# tick-box-1591A-mk-5_0.net
KiCad netlist of a schematic drawn in EAGLE
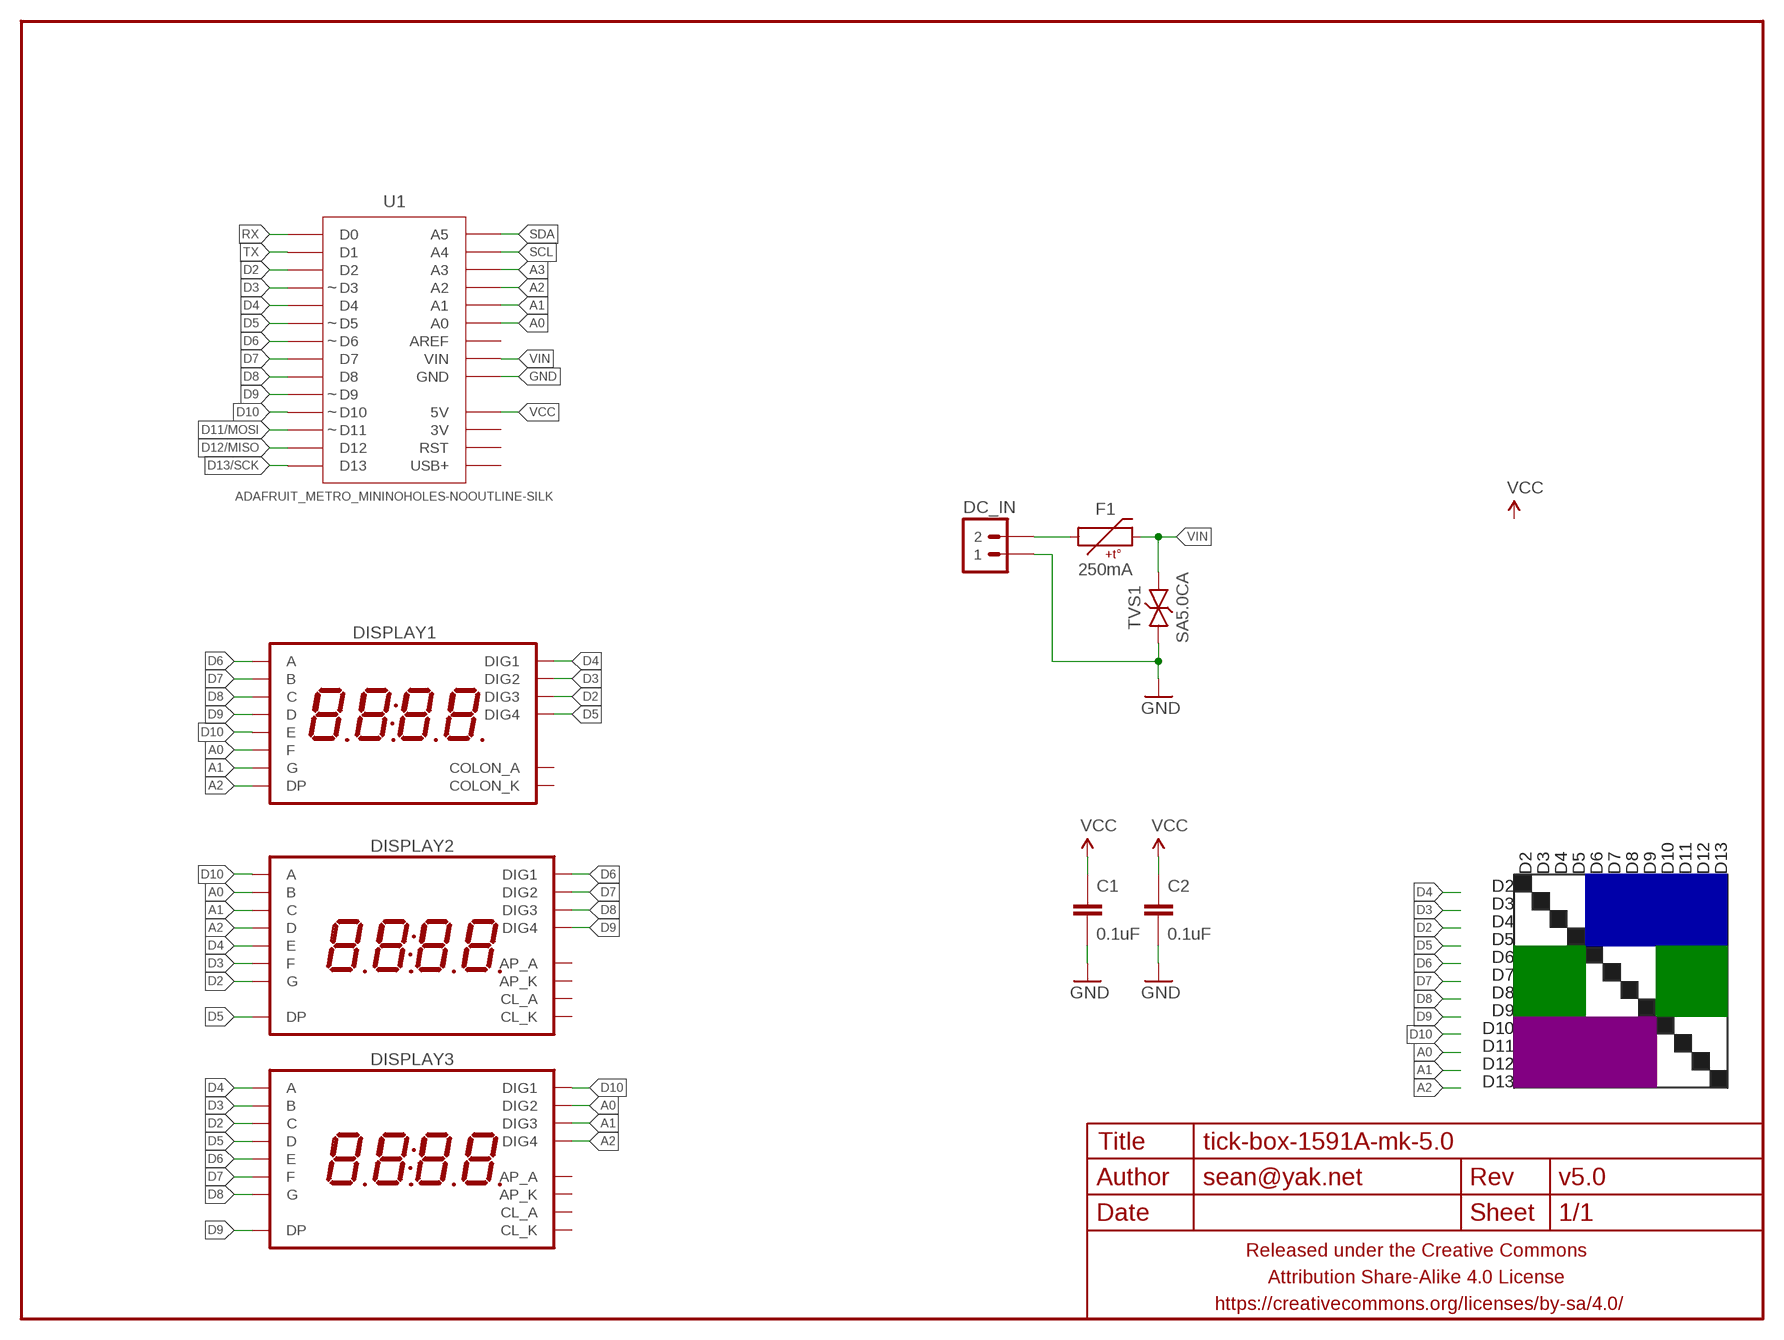
[diagram p0: schematic, sheet 1]

(export (version "E")
  (design (tool "Eeschema 10.0.6"))
  (components
    (comp (ref "C1")
      (value "0.1uF")
      (footprint "eagle-import:C0603")
      (libsource (lib "eagle-import") (part "CAPACITOR-CERAMICC0603"))
    )
    (comp (ref "C2")
      (value "0.1uF")
      (footprint "eagle-import:C0603")
      (libsource (lib "eagle-import") (part "CAPACITOR-CERAMICC0603"))
    )
    (comp (ref "DC_IN")
      (value "M02PTH-CENTERED-R+")
      (footprint "eagle-import:1X02-CENTER-R+")
      (libsource (lib "eagle-import") (part "M02PTH-CENTERED-R+"))
    )
    (comp (ref "DISPLAY1")
      (value "7SEG_4DIGIT_COLON14.2MM-CC-NS")
      (footprint "eagle-import:7SEG_4DIG_NS")
      (libsource (lib "eagle-import") (part "7SEG_4DIGIT_COLON14.2MM-CC-NS"))
    )
    (comp (ref "DISPLAY2")
      (value "7SEG_4DIGIT_COLON_APOS")
      (footprint "eagle-import:7SEG_4DIG_10MM")
      (libsource (lib "eagle-import") (part "7SEG_4DIGIT_COLON_APOS"))
    )
    (comp (ref "DISPLAY3")
      (value "7SEG_4DIGIT_COLON_APOS")
      (footprint "eagle-import:7SEG_4DIG_10MM")
      (libsource (lib "eagle-import") (part "7SEG_4DIGIT_COLON_APOS"))
    )
    (comp (ref "F1")
      (value "250mA")
      (footprint "eagle-import:PTC-1210")
      (libsource (lib "eagle-import") (part "PTCPTC-1210"))
    )
    (comp (ref "FRAME1")
      (value "FRAME-LETTERNO_PACKAGE")
      (footprint "eagle-import:DUMMY")
      (fields (field (name "DESIGNER") "sean@yak.net") (field (name "VERSION") "v5.0"))
      (libsource (lib "eagle-import") (part "FRAME-LETTERNO_PACKAGE"))
    )
    (comp (ref "TVS1")
      (value "SA5.0CA")
      (footprint "eagle-import:SMA-DIODE-TVS-BIDIR")
      (libsource (lib "eagle-import") (part "TVSSMA"))
    )
    (comp (ref "U1")
      (value "ADAFRUIT_METRO_MININOHOLES-NOOUTLINE-SILK")
      (footprint "eagle-import:ADAFRUIT_METRO_MINI")
      (libsource (lib "eagle-import") (part "ADAFRUIT_METRO_MININOHOLES-NOOUTLINE-SILK"))
    )
  )
  (nets
    (net (code "1") (name "A0") (class "Default")
      (node (ref "DISPLAY1") (pin "P$12") (pinfunction "F_P$12") (pintype "passive"))
      (node (ref "DISPLAY2") (pin "16") (pinfunction "B_16") (pintype "passive"))
      (node (ref "DISPLAY3") (pin "2") (pinfunction "DIG2_2") (pintype "passive"))
      (node (ref "U1") (pin "23") (pinfunction "A0_23") (pintype "bidirectional"))
    )
    (net (code "2") (name "A1") (class "Default")
      (node (ref "DISPLAY1") (pin "P$5") (pinfunction "G_P$5") (pintype "passive"))
      (node (ref "DISPLAY2") (pin "13") (pinfunction "C_13") (pintype "passive"))
      (node (ref "DISPLAY3") (pin "6") (pinfunction "DIG3_6") (pintype "passive"))
      (node (ref "U1") (pin "24") (pinfunction "A1_24") (pintype "bidirectional"))
    )
    (net (code "3") (name "A2") (class "Default")
      (node (ref "DISPLAY1") (pin "P$3") (pinfunction "DP_P$3") (pintype "passive"))
      (node (ref "DISPLAY2") (pin "3") (pinfunction "D_3") (pintype "passive"))
      (node (ref "DISPLAY3") (pin "8") (pinfunction "DIG4_8") (pintype "passive"))
      (node (ref "U1") (pin "25") (pinfunction "A2_25") (pintype "bidirectional"))
    )
    (net (code "4") (name "A3") (class "Default")
      (node (ref "U1") (pin "26") (pinfunction "A3_26") (pintype "bidirectional"))
    )
    (net (code "5") (name "D2") (class "Default")
      (node (ref "DISPLAY1") (pin "P$10") (pinfunction "DIG3_P$10") (pintype "passive"))
      (node (ref "DISPLAY2") (pin "15") (pinfunction "G_15") (pintype "passive"))
      (node (ref "DISPLAY3") (pin "13") (pinfunction "C_13") (pintype "passive"))
      (node (ref "U1") (pin "3") (pinfunction "D2_3") (pintype "bidirectional"))
    )
    (net (code "6") (name "D3") (class "Default")
      (node (ref "DISPLAY1") (pin "P$11") (pinfunction "DIG2_P$11") (pintype "passive"))
      (node (ref "DISPLAY2") (pin "11") (pinfunction "F_11") (pintype "passive"))
      (node (ref "DISPLAY3") (pin "16") (pinfunction "B_16") (pintype "passive"))
      (node (ref "U1") (pin "4") (pinfunction "D3_4") (pintype "bidirectional"))
    )
    (net (code "7") (name "D4") (class "Default")
      (node (ref "DISPLAY1") (pin "P$14") (pinfunction "DIG1_P$14") (pintype "passive"))
      (node (ref "DISPLAY2") (pin "5") (pinfunction "E_5") (pintype "passive"))
      (node (ref "DISPLAY3") (pin "14") (pinfunction "A_14") (pintype "passive"))
      (node (ref "U1") (pin "5") (pinfunction "D4_5") (pintype "bidirectional"))
    )
    (net (code "8") (name "D5") (class "Default")
      (node (ref "DISPLAY1") (pin "P$6") (pinfunction "DIG4_P$6") (pintype "passive"))
      (node (ref "DISPLAY2") (pin "7") (pinfunction "DP_7") (pintype "passive"))
      (node (ref "DISPLAY3") (pin "3") (pinfunction "D_3") (pintype "passive"))
      (node (ref "U1") (pin "6") (pinfunction "D5_6") (pintype "bidirectional"))
    )
    (net (code "9") (name "D6") (class "Default")
      (node (ref "DISPLAY1") (pin "P$13") (pinfunction "A_P$13") (pintype "passive"))
      (node (ref "DISPLAY2") (pin "1") (pinfunction "DIG1_1") (pintype "passive"))
      (node (ref "DISPLAY3") (pin "5") (pinfunction "E_5") (pintype "passive"))
      (node (ref "U1") (pin "7") (pinfunction "D6_7") (pintype "bidirectional"))
    )
    (net (code "10") (name "D7") (class "Default")
      (node (ref "DISPLAY1") (pin "P$9") (pinfunction "B_P$9") (pintype "passive"))
      (node (ref "DISPLAY2") (pin "2") (pinfunction "DIG2_2") (pintype "passive"))
      (node (ref "DISPLAY3") (pin "11") (pinfunction "F_11") (pintype "passive"))
      (node (ref "U1") (pin "8") (pinfunction "D7_8") (pintype "bidirectional"))
    )
    (net (code "11") (name "D8") (class "Default")
      (node (ref "DISPLAY1") (pin "P$4") (pinfunction "C_P$4") (pintype "passive"))
      (node (ref "DISPLAY2") (pin "6") (pinfunction "DIG3_6") (pintype "passive"))
      (node (ref "DISPLAY3") (pin "15") (pinfunction "G_15") (pintype "passive"))
      (node (ref "U1") (pin "9") (pinfunction "D8_9") (pintype "bidirectional"))
    )
    (net (code "12") (name "D9") (class "Default")
      (node (ref "DISPLAY1") (pin "P$2") (pinfunction "D_P$2") (pintype "passive"))
      (node (ref "DISPLAY2") (pin "8") (pinfunction "DIG4_8") (pintype "passive"))
      (node (ref "DISPLAY3") (pin "7") (pinfunction "DP_7") (pintype "passive"))
      (node (ref "U1") (pin "10") (pinfunction "D9_10") (pintype "bidirectional"))
    )
    (net (code "13") (name "D10") (class "Default")
      (node (ref "DISPLAY1") (pin "P$1") (pinfunction "E_P$1") (pintype "passive"))
      (node (ref "DISPLAY2") (pin "14") (pinfunction "A_14") (pintype "passive"))
      (node (ref "DISPLAY3") (pin "1") (pinfunction "DIG1_1") (pintype "passive"))
      (node (ref "U1") (pin "11") (pinfunction "D10_11") (pintype "bidirectional"))
    )
    (net (code "14") (name "D11{slash}MOSI") (class "Default")
      (node (ref "U1") (pin "12") (pinfunction "D11_12") (pintype "bidirectional"))
    )
    (net (code "15") (name "D12{slash}MISO") (class "Default")
      (node (ref "U1") (pin "13") (pinfunction "D12_13") (pintype "bidirectional"))
    )
    (net (code "16") (name "D13{slash}SCK") (class "Default")
      (node (ref "U1") (pin "14") (pinfunction "D13_14") (pintype "bidirectional"))
    )
    (net (code "17") (name "GND") (class "Default")
      (node (ref "C1") (pin "2") (pinfunction "2_2") (pintype "passive"))
      (node (ref "C2") (pin "2") (pinfunction "2_2") (pintype "passive"))
      (node (ref "DC_IN") (pin "1") (pinfunction "1_1") (pintype "passive"))
      (node (ref "TVS1") (pin "1") (pinfunction "1_1") (pintype "passive"))
      (node (ref "U1") (pin "19") (pinfunction "GND_19") (pintype "bidirectional"))
      (node (ref "U1") (pin "20") (pinfunction "GND_20") (pintype "bidirectional"))
    )
    (net (code "18") (name "Net-(DC_IN-Pad2)") (class "Default")
      (node (ref "DC_IN") (pin "2") (pinfunction "2_2") (pintype "passive"))
      (node (ref "F1") (pin "1") (pinfunction "1_1") (pintype "passive"))
    )
    (net (code "19") (name "RX") (class "Default")
      (node (ref "U1") (pin "1") (pinfunction "D0_1") (pintype "bidirectional"))
    )
    (net (code "20") (name "SCL") (class "Default")
      (node (ref "U1") (pin "27") (pinfunction "A4_27") (pintype "bidirectional"))
    )
    (net (code "21") (name "SDA") (class "Default")
      (node (ref "U1") (pin "28") (pinfunction "A5_28") (pintype "bidirectional"))
    )
    (net (code "22") (name "TX") (class "Default")
      (node (ref "U1") (pin "2") (pinfunction "D1_2") (pintype "bidirectional"))
    )
    (net (code "23") (name "VCC") (class "Default")
      (node (ref "C1") (pin "1") (pinfunction "1_1") (pintype "passive"))
      (node (ref "C2") (pin "1") (pinfunction "1_1") (pintype "passive"))
      (node (ref "U1") (pin "18") (pinfunction "5V_18") (pintype "bidirectional"))
    )
    (net (code "24") (name "VIN") (class "Default")
      (node (ref "F1") (pin "2") (pinfunction "2_2") (pintype "passive"))
      (node (ref "TVS1") (pin "2") (pinfunction "2_2") (pintype "passive"))
      (node (ref "U1") (pin "21") (pinfunction "VIN_21") (pintype "bidirectional"))
    )
    (net (code "25") (name "unconnected-(DISPLAY1-COLON_A-PadP$8)") (class "Default")
      (node (ref "DISPLAY1") (pin "P$8") (pinfunction "COLON_A_P$8") (pintype "passive"))
    )
    (net (code "26") (name "unconnected-(DISPLAY1-COLON_K-PadP$7)") (class "Default")
      (node (ref "DISPLAY1") (pin "P$7") (pinfunction "COLON_K_P$7") (pintype "passive"))
    )
    (net (code "27") (name "unconnected-(DISPLAY2-AP_A-Pad10)") (class "Default")
      (node (ref "DISPLAY2") (pin "10") (pinfunction "AP_A_10") (pintype "bidirectional"))
    )
    (net (code "28") (name "unconnected-(DISPLAY2-AP_K-Pad9)") (class "Default")
      (node (ref "DISPLAY2") (pin "9") (pinfunction "AP_K_9") (pintype "bidirectional"))
    )
    (net (code "29") (name "unconnected-(DISPLAY2-CL_A-Pad4)") (class "Default")
      (node (ref "DISPLAY2") (pin "4") (pinfunction "CL_A_4") (pintype "passive"))
    )
    (net (code "30") (name "unconnected-(DISPLAY2-CL_K-Pad12)") (class "Default")
      (node (ref "DISPLAY2") (pin "12") (pinfunction "CL_K_12") (pintype "passive"))
    )
    (net (code "31") (name "unconnected-(DISPLAY3-AP_A-Pad10)") (class "Default")
      (node (ref "DISPLAY3") (pin "10") (pinfunction "AP_A_10") (pintype "bidirectional"))
    )
    (net (code "32") (name "unconnected-(DISPLAY3-AP_K-Pad9)") (class "Default")
      (node (ref "DISPLAY3") (pin "9") (pinfunction "AP_K_9") (pintype "bidirectional"))
    )
    (net (code "33") (name "unconnected-(DISPLAY3-CL_A-Pad4)") (class "Default")
      (node (ref "DISPLAY3") (pin "4") (pinfunction "CL_A_4") (pintype "passive"))
    )
    (net (code "34") (name "unconnected-(DISPLAY3-CL_K-Pad12)") (class "Default")
      (node (ref "DISPLAY3") (pin "12") (pinfunction "CL_K_12") (pintype "passive"))
    )
    (net (code "35") (name "unconnected-(U1-3V-Pad17)") (class "Default")
      (node (ref "U1") (pin "17") (pinfunction "3V_17") (pintype "bidirectional"))
    )
    (net (code "36") (name "unconnected-(U1-AREF-Pad22)") (class "Default")
      (node (ref "U1") (pin "22") (pinfunction "AREF_22") (pintype "bidirectional"))
    )
    (net (code "37") (name "unconnected-(U1-RST-Pad16)") (class "Default")
      (node (ref "U1") (pin "16") (pinfunction "RST_16") (pintype "bidirectional"))
    )
    (net (code "38") (name "unconnected-(U1-USB+-Pad15)") (class "Default")
      (node (ref "U1") (pin "15") (pinfunction "USB+_15") (pintype "bidirectional"))
    )
  )
)
